# ece411_t2_schematic_4.net
KiCad netlist of a schematic drawn in EAGLE
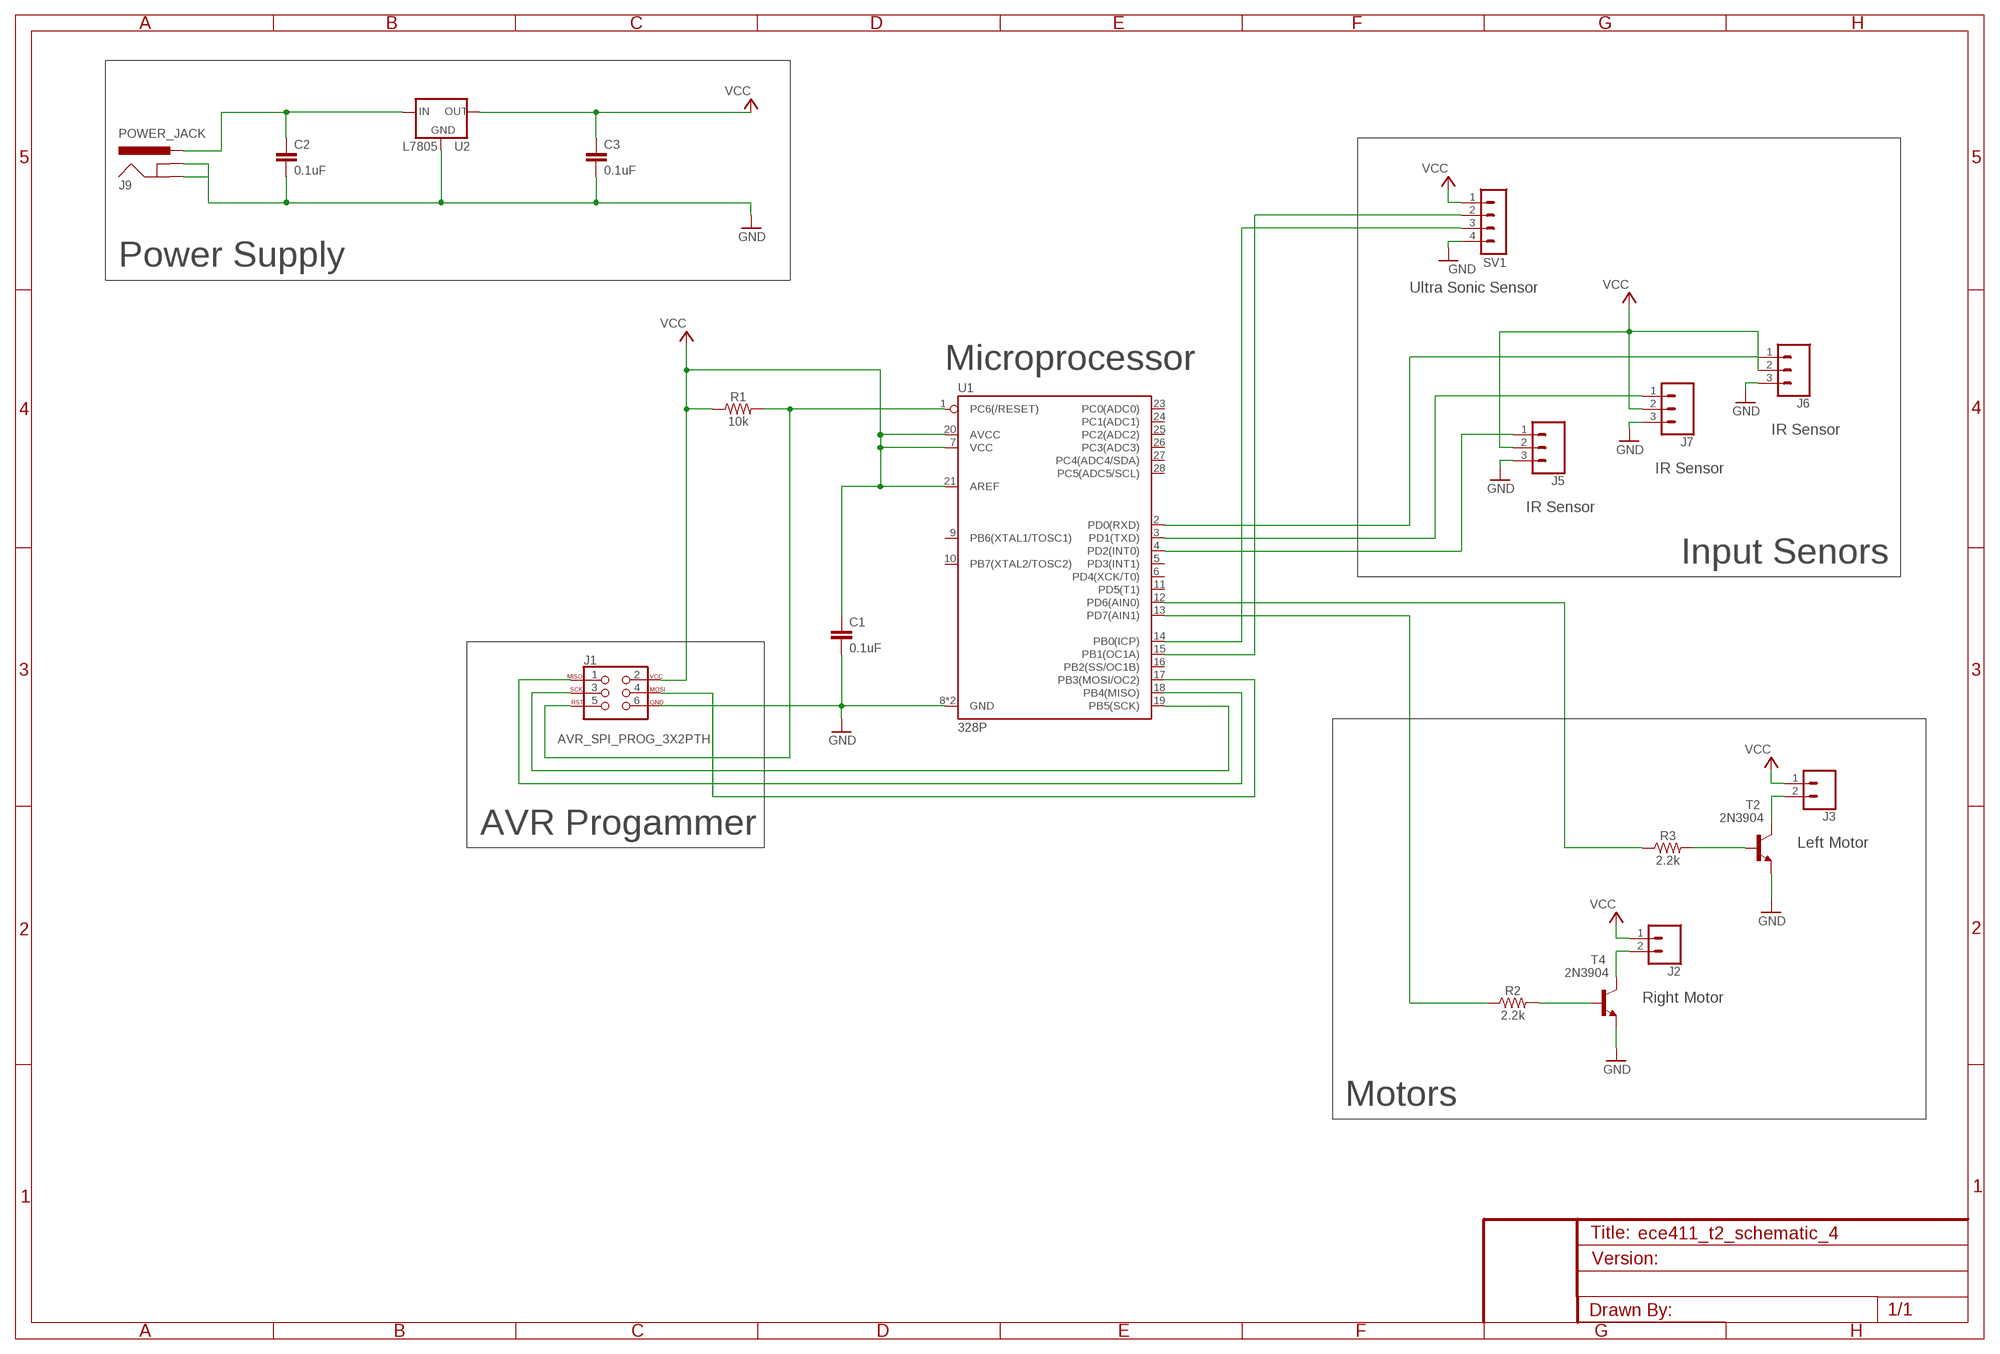
[diagram p0: schematic, sheet 1]

(export (version "E")
  (design (tool "Eeschema 10.0.6"))
  (components
    (comp (ref "C1")
      (value "0.1uF")
      (footprint "eagle-import:0402")
      (libsource (lib "eagle-import") (part "0.1UF-0402-6.3V-10%-X7R"))
    )
    (comp (ref "C2")
      (value "0.1uF")
      (footprint "eagle-import:0402")
      (libsource (lib "eagle-import") (part "0.1UF-0402-6.3V-10%-X7R"))
    )
    (comp (ref "C3")
      (value "0.1uF")
      (footprint "eagle-import:0402")
      (libsource (lib "eagle-import") (part "0.1UF-0402-6.3V-10%-X7R"))
    )
    (comp (ref "J1")
      (value "AVR_SPI_PROG_3X2PTH")
      (footprint "eagle-import:2X3")
      (libsource (lib "eagle-import") (part "AVR_SPI_PROG_3X2PTH"))
    )
    (comp (ref "J2")
      (value "CONN_02")
      (footprint "eagle-import:1X02")
      (libsource (lib "eagle-import") (part "CONN_02"))
    )
    (comp (ref "J3")
      (value "CONN_02")
      (footprint "eagle-import:1X02")
      (libsource (lib "eagle-import") (part "CONN_02"))
    )
    (comp (ref "J5")
      (value "455-1750-1-ND")
      (footprint "eagle-import:1X03")
      (libsource (lib "eagle-import") (part "CONN_03"))
    )
    (comp (ref "J6")
      (value "455-1750-1-ND")
      (footprint "eagle-import:1X03")
      (libsource (lib "eagle-import") (part "CONN_03"))
    )
    (comp (ref "J7")
      (value "455-1750-1-ND")
      (footprint "eagle-import:1X03")
      (libsource (lib "eagle-import") (part "CONN_03"))
    )
    (comp (ref "J9")
      (value "POWER_JACK")
      (footprint "eagle-import:POWER_JACK_PTH")
      (libsource (lib "eagle-import") (part "POWER_JACK"))
    )
    (comp (ref "R1")
      (value "10k")
      (footprint "eagle-import:0402")
      (libsource (lib "eagle-import") (part "10KOHM-0402-1/16W-1%"))
    )
    (comp (ref "R2")
      (value "2.2k")
      (footprint "eagle-import:0603")
      (libsource (lib "eagle-import") (part "2.2KOHM-0603-1/10W-1%"))
    )
    (comp (ref "R3")
      (value "2.2k")
      (footprint "eagle-import:0603")
      (libsource (lib "eagle-import") (part "2.2KOHM-0603-1/10W-1%"))
    )
    (comp (ref "SV1")
      (value "MA04-1")
      (footprint "eagle-import:MA04-1")
      (libsource (lib "eagle-import") (part "MA04-1"))
    )
    (comp (ref "T2")
      (value "2N3904")
      (footprint "eagle-import:TO92")
      (libsource (lib "eagle-import") (part "2N3904"))
    )
    (comp (ref "T4")
      (value "2N3904")
      (footprint "eagle-import:TO92")
      (libsource (lib "eagle-import") (part "2N3904"))
    )
    (comp (ref "U1")
      (value "328P")
      (footprint "eagle-import:DIP28")
      (libsource (lib "eagle-import") (part "ATMEGA328P_PDIP"))
    )
    (comp (ref "U2")
      (value "V_REG_78XX-TO-220")
      (footprint "eagle-import:TO-220-ALT")
      (libsource (lib "eagle-import") (part "V_REG_78XX-TO-220"))
    )
  )
  (nets
    (net (code "1") (name "GND") (class "Default")
      (node (ref "C1") (pin "2") (pinfunction "2_2") (pintype "passive"))
      (node (ref "C2") (pin "2") (pinfunction "2_2") (pintype "passive"))
      (node (ref "C3") (pin "2") (pinfunction "2_2") (pintype "passive"))
      (node (ref "J1") (pin "6") (pinfunction "6_6") (pintype "passive"))
      (node (ref "J5") (pin "3") (pinfunction "3_3") (pintype "passive"))
      (node (ref "J6") (pin "3") (pinfunction "3_3") (pintype "passive"))
      (node (ref "J7") (pin "3") (pinfunction "3_3") (pintype "passive"))
      (node (ref "J9") (pin "GNDBREAK") (pinfunction "GNDBREAK_GNDBREAK") (pintype "bidirectional"))
      (node (ref "SV1") (pin "4") (pinfunction "4_4") (pintype "passive"))
      (node (ref "T2") (pin "3") (pinfunction "E_3") (pintype "passive"))
      (node (ref "T4") (pin "3") (pinfunction "E_3") (pintype "passive"))
      (node (ref "U1") (pin "22") (pinfunction "GND_22") (pintype "bidirectional"))
      (node (ref "U1") (pin "8") (pinfunction "GND_8") (pintype "bidirectional"))
      (node (ref "U2") (pin "GND") (pinfunction "GND_GND") (pintype "input"))
    )
    (net (code "2") (name "Net-(C2-Pad1)") (class "Default")
      (node (ref "C2") (pin "1") (pinfunction "1_1") (pintype "passive"))
      (node (ref "J9") (pin "PWR") (pinfunction "PWR_PWR") (pintype "bidirectional"))
      (node (ref "U2") (pin "IN") (pinfunction "IN_IN") (pintype "input"))
    )
    (net (code "3") (name "Net-(T2-B)") (class "Default")
      (node (ref "R3") (pin "2") (pinfunction "2_2") (pintype "passive"))
      (node (ref "T2") (pin "2") (pinfunction "B_2") (pintype "passive"))
    )
    (net (code "4") (name "Net-(T2-C)") (class "Default")
      (node (ref "J3") (pin "2") (pinfunction "2_2") (pintype "passive"))
      (node (ref "T2") (pin "1") (pinfunction "C_1") (pintype "passive"))
    )
    (net (code "5") (name "Net-(T4-B)") (class "Default")
      (node (ref "R2") (pin "2") (pinfunction "2_2") (pintype "passive"))
      (node (ref "T4") (pin "2") (pinfunction "B_2") (pintype "passive"))
    )
    (net (code "6") (name "Net-(U1-PB0(ICP))") (class "Default")
      (node (ref "SV1") (pin "3") (pinfunction "3_3") (pintype "passive"))
      (node (ref "U1") (pin "14") (pinfunction "PB0(ICP)_14") (pintype "bidirectional"))
    )
    (net (code "7") (name "Net-(U1-PB1(OC1A))") (class "Default")
      (node (ref "SV1") (pin "2") (pinfunction "2_2") (pintype "passive"))
      (node (ref "U1") (pin "15") (pinfunction "PB1(OC1A)_15") (pintype "bidirectional"))
    )
    (net (code "8") (name "Net-(U1-PB3(MOSI{slash}OC2))") (class "Default")
      (node (ref "J1") (pin "4") (pinfunction "4_4") (pintype "passive"))
      (node (ref "U1") (pin "17") (pinfunction "PB3(MOSI/OC2)_17") (pintype "bidirectional"))
    )
    (net (code "9") (name "Net-(U1-PB4(MISO))") (class "Default")
      (node (ref "J1") (pin "1") (pinfunction "1_1") (pintype "passive"))
      (node (ref "U1") (pin "18") (pinfunction "PB4(MISO)_18") (pintype "bidirectional"))
    )
    (net (code "10") (name "Net-(U1-PB5(SCK))") (class "Default")
      (node (ref "J1") (pin "3") (pinfunction "3_3") (pintype "passive"))
      (node (ref "U1") (pin "19") (pinfunction "PB5(SCK)_19") (pintype "bidirectional"))
    )
    (net (code "11") (name "Net-(U1-PC6({slash}RESET))") (class "Default")
      (node (ref "J1") (pin "5") (pinfunction "5_5") (pintype "passive"))
      (node (ref "R1") (pin "2") (pinfunction "2_2") (pintype "passive"))
      (node (ref "U1") (pin "1") (pinfunction "PC6(/RESET)_1") (pintype "bidirectional"))
    )
    (net (code "12") (name "Net-(U1-PD0(RXD))") (class "Default")
      (node (ref "J6") (pin "1") (pinfunction "1_1") (pintype "passive"))
      (node (ref "U1") (pin "2") (pinfunction "PD0(RXD)_2") (pintype "bidirectional"))
    )
    (net (code "13") (name "Net-(U1-PD1(TXD))") (class "Default")
      (node (ref "J7") (pin "1") (pinfunction "1_1") (pintype "passive"))
      (node (ref "U1") (pin "3") (pinfunction "PD1(TXD)_3") (pintype "bidirectional"))
    )
    (net (code "14") (name "Net-(U1-PD2(INT0))") (class "Default")
      (node (ref "J5") (pin "1") (pinfunction "1_1") (pintype "passive"))
      (node (ref "U1") (pin "4") (pinfunction "PD2(INT0)_4") (pintype "bidirectional"))
    )
    (net (code "15") (name "Net-(U1-PD6(AIN0))") (class "Default")
      (node (ref "R3") (pin "1") (pinfunction "1_1") (pintype "passive"))
      (node (ref "U1") (pin "12") (pinfunction "PD6(AIN0)_12") (pintype "bidirectional"))
    )
    (net (code "16") (name "Net-(U1-PD7(AIN1))") (class "Default")
      (node (ref "R2") (pin "1") (pinfunction "1_1") (pintype "passive"))
      (node (ref "U1") (pin "13") (pinfunction "PD7(AIN1)_13") (pintype "bidirectional"))
    )
    (net (code "17") (name "VCC") (class "Default")
      (node (ref "C1") (pin "1") (pinfunction "1_1") (pintype "passive"))
      (node (ref "C3") (pin "1") (pinfunction "1_1") (pintype "passive"))
      (node (ref "J1") (pin "2") (pinfunction "2_2") (pintype "passive"))
      (node (ref "J2") (pin "1") (pinfunction "1_1") (pintype "passive"))
      (node (ref "J2") (pin "2") (pinfunction "2_2") (pintype "passive"))
      (node (ref "J3") (pin "1") (pinfunction "1_1") (pintype "passive"))
      (node (ref "J5") (pin "2") (pinfunction "2_2") (pintype "passive"))
      (node (ref "J6") (pin "2") (pinfunction "2_2") (pintype "passive"))
      (node (ref "J7") (pin "2") (pinfunction "2_2") (pintype "passive"))
      (node (ref "R1") (pin "1") (pinfunction "1_1") (pintype "passive"))
      (node (ref "SV1") (pin "1") (pinfunction "1_1") (pintype "passive"))
      (node (ref "T4") (pin "1") (pinfunction "C_1") (pintype "passive"))
      (node (ref "U1") (pin "20") (pinfunction "AVCC_20") (pintype "bidirectional"))
      (node (ref "U1") (pin "21") (pinfunction "AREF_21") (pintype "bidirectional"))
      (node (ref "U1") (pin "7") (pinfunction "VCC_7") (pintype "bidirectional"))
      (node (ref "U2") (pin "OUT") (pinfunction "OUT_OUT") (pintype "passive"))
    )
    (net (code "18") (name "unconnected-(J9-PadGND)") (class "Default")
      (node (ref "J9") (pin "GND") (pinfunction "GND_GND") (pintype "bidirectional"))
    )
    (net (code "19") (name "unconnected-(U1-PB2(SS{slash}OC1B)-Pad16)") (class "Default")
      (node (ref "U1") (pin "16") (pinfunction "PB2(SS/OC1B)_16") (pintype "bidirectional"))
    )
    (net (code "20") (name "unconnected-(U1-PB6(XTAL1{slash}TOSC1)-Pad9)") (class "Default")
      (node (ref "U1") (pin "9") (pinfunction "PB6(XTAL1/TOSC1)_9") (pintype "bidirectional"))
    )
    (net (code "21") (name "unconnected-(U1-PB7(XTAL2{slash}TOSC2)-Pad10)") (class "Default")
      (node (ref "U1") (pin "10") (pinfunction "PB7(XTAL2/TOSC2)_10") (pintype "bidirectional"))
    )
    (net (code "22") (name "unconnected-(U1-PC0(ADC0)-Pad23)") (class "Default")
      (node (ref "U1") (pin "23") (pinfunction "PC0(ADC0)_23") (pintype "bidirectional"))
    )
    (net (code "23") (name "unconnected-(U1-PC1(ADC1)-Pad24)") (class "Default")
      (node (ref "U1") (pin "24") (pinfunction "PC1(ADC1)_24") (pintype "bidirectional"))
    )
    (net (code "24") (name "unconnected-(U1-PC2(ADC2)-Pad25)") (class "Default")
      (node (ref "U1") (pin "25") (pinfunction "PC2(ADC2)_25") (pintype "bidirectional"))
    )
    (net (code "25") (name "unconnected-(U1-PC3(ADC3)-Pad26)") (class "Default")
      (node (ref "U1") (pin "26") (pinfunction "PC3(ADC3)_26") (pintype "bidirectional"))
    )
    (net (code "26") (name "unconnected-(U1-PC4(ADC4{slash}SDA)-Pad27)") (class "Default")
      (node (ref "U1") (pin "27") (pinfunction "PC4(ADC4/SDA)_27") (pintype "bidirectional"))
    )
    (net (code "27") (name "unconnected-(U1-PC5(ADC5{slash}SCL)-Pad28)") (class "Default")
      (node (ref "U1") (pin "28") (pinfunction "PC5(ADC5/SCL)_28") (pintype "bidirectional"))
    )
    (net (code "28") (name "unconnected-(U1-PD3(INT1)-Pad5)") (class "Default")
      (node (ref "U1") (pin "5") (pinfunction "PD3(INT1)_5") (pintype "bidirectional"))
    )
    (net (code "29") (name "unconnected-(U1-PD4(XCK{slash}T0)-Pad6)") (class "Default")
      (node (ref "U1") (pin "6") (pinfunction "PD4(XCK/T0)_6") (pintype "bidirectional"))
    )
    (net (code "30") (name "unconnected-(U1-PD5(T1)-Pad11)") (class "Default")
      (node (ref "U1") (pin "11") (pinfunction "PD5(T1)_11") (pintype "bidirectional"))
    )
  )
)
